# LONGAN_CORE.net
KiCad netlist of a schematic drawn in EAGLE
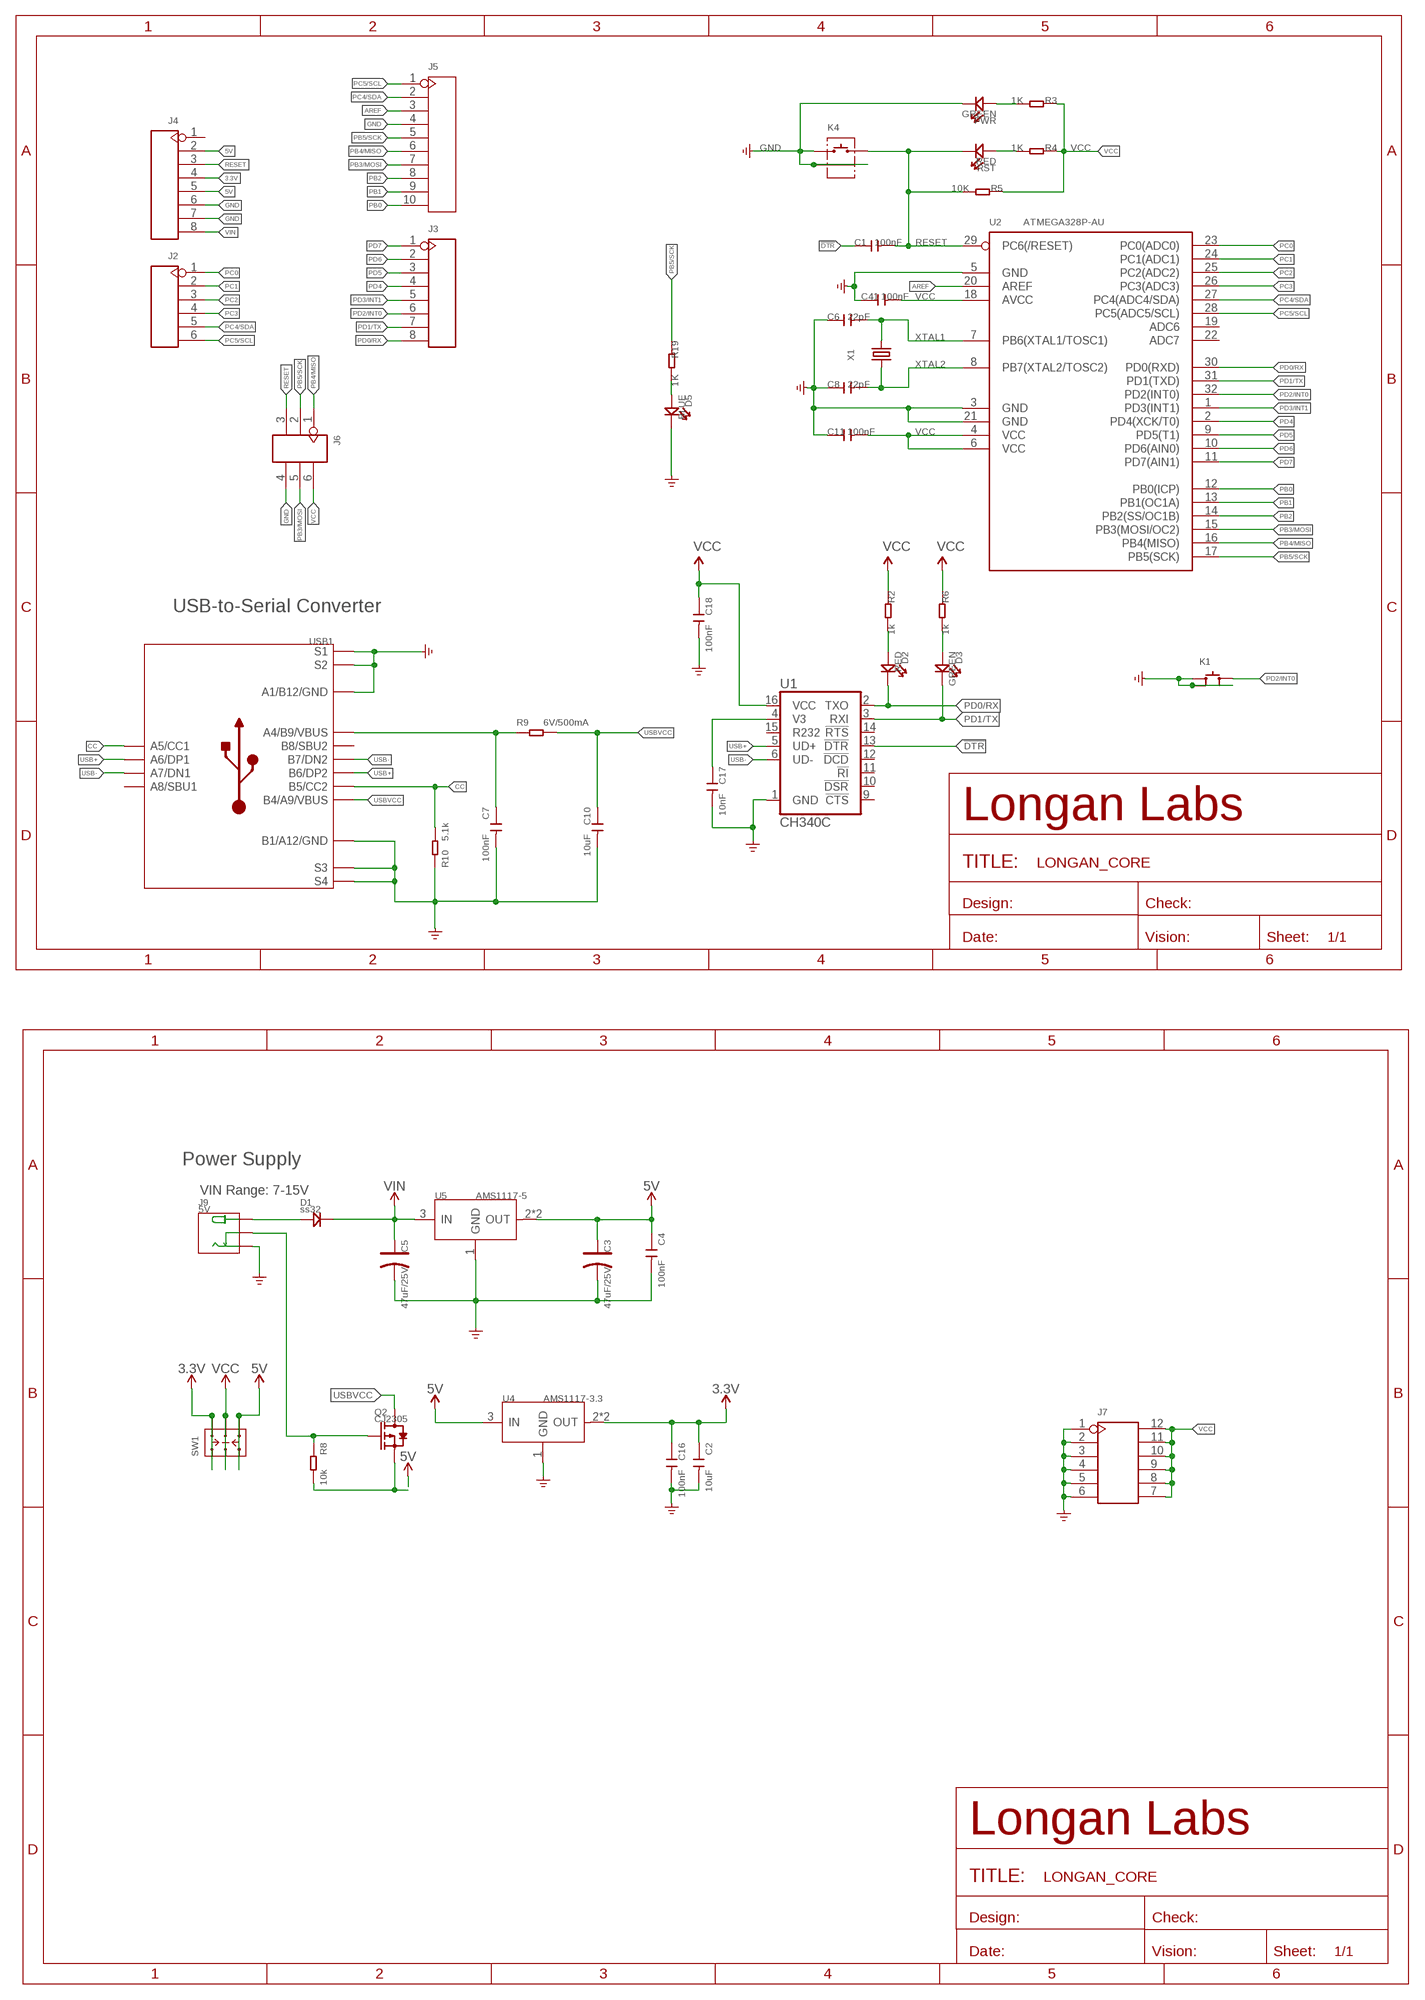
[diagram p0: schematic, sheet 1]

(export (version "E")
  (design (tool "Eeschema 10.0.6"))
  (components
    (comp (ref "C1")
      (value "100nF")
      (footprint "eagle-import:C0603")
      (libsource (lib "eagle-import") (part "C-0603"))
    )
    (comp (ref "C2")
      (value "10uF")
      (footprint "eagle-import:C0603")
      (libsource (lib "eagle-import") (part "CAP-0603"))
    )
    (comp (ref "C3")
      (value "47uF/25V")
      (footprint "eagle-import:ELECTRO-SMD-C-6MM")
      (libsource (lib "eagle-import") (part "CAP-POLAR-ELECTRO-C"))
    )
    (comp (ref "C4")
      (value "100nF")
      (footprint "eagle-import:C0603")
      (libsource (lib "eagle-import") (part "CAP-0603"))
    )
    (comp (ref "C5")
      (value "47uF/25V")
      (footprint "eagle-import:ELECTRO-SMD-C-6MM")
      (libsource (lib "eagle-import") (part "CAP-POLAR-ELECTRO-C"))
    )
    (comp (ref "C6")
      (value "22pF")
      (footprint "eagle-import:C0603")
      (libsource (lib "eagle-import") (part "C-0603"))
    )
    (comp (ref "C7")
      (value "100nF")
      (footprint "eagle-import:C0603")
      (libsource (lib "eagle-import") (part "CAP-0603"))
    )
    (comp (ref "C8")
      (value "22pF")
      (footprint "eagle-import:C0603")
      (libsource (lib "eagle-import") (part "C-0603"))
    )
    (comp (ref "C10")
      (value "10uF")
      (footprint "eagle-import:C0603")
      (libsource (lib "eagle-import") (part "CAP-0603"))
    )
    (comp (ref "C11")
      (value "100nF")
      (footprint "eagle-import:C0603")
      (libsource (lib "eagle-import") (part "C-0603"))
    )
    (comp (ref "C16")
      (value "100nF")
      (footprint "eagle-import:C0603")
      (libsource (lib "eagle-import") (part "CAP-0603"))
    )
    (comp (ref "C17")
      (value "10nF")
      (footprint "eagle-import:C0603")
      (libsource (lib "eagle-import") (part "CAP-0603"))
    )
    (comp (ref "C18")
      (value "100nF")
      (footprint "eagle-import:C0603")
      (libsource (lib "eagle-import") (part "CAP-0603"))
    )
    (comp (ref "C41")
      (value "100nF")
      (footprint "eagle-import:C0603")
      (libsource (lib "eagle-import") (part "C-0603"))
    )
    (comp (ref "D1")
      (value "ss32")
      (footprint "eagle-import:DO-214AC")
      (libsource (lib "eagle-import") (part "DIODE'SMA'"))
    )
    (comp (ref "D2")
      (value "RED")
      (footprint "eagle-import:LED-0603")
      (libsource (lib "eagle-import") (part "LED'0603'"))
    )
    (comp (ref "D3")
      (value "GREEN")
      (footprint "eagle-import:LED-0603")
      (libsource (lib "eagle-import") (part "LED'0603'"))
    )
    (comp (ref "D5")
      (value "BLUE")
      (footprint "eagle-import:LED-0603")
      (libsource (lib "eagle-import") (part "LED'0603'"))
    )
    (comp (ref "J2")
      (value "HEADER-6P-55/35MIL")
      (footprint "eagle-import:H6-2.54")
      (libsource (lib "eagle-import") (part "HEADER-6P-55/35MIL"))
    )
    (comp (ref "J3")
      (value "HEADER-8P-65/35MIL")
      (footprint "eagle-import:H8-2.54-C65D35MIL")
      (libsource (lib "eagle-import") (part "HEADER-8P-65/35MIL"))
    )
    (comp (ref "J4")
      (value "HEADER-8P-65/35MIL")
      (footprint "eagle-import:H8-2.54-C65D35MIL")
      (libsource (lib "eagle-import") (part "HEADER-8P-65/35MIL"))
    )
    (comp (ref "J5")
      (value "HEADER-10P-2.54")
      (footprint "eagle-import:H10-2.54")
      (libsource (lib "eagle-import") (part "HEADER-10P-2.54"))
    )
    (comp (ref "J6")
      (value "HEADER-2X3P-2.54")
      (footprint "eagle-import:H2X3-2.54")
      (libsource (lib "eagle-import") (part "HEADER-2X3P-2.54"))
    )
    (comp (ref "J7")
      (value "HEADER-2X6P-2.54")
      (footprint "eagle-import:H2X6-2.54")
      (libsource (lib "eagle-import") (part "HEADER-2X6P-2.54"))
    )
    (comp (ref "J9")
      (value "5V")
      (footprint "eagle-import:DCJ3P-14.2X11.0X9.0MM")
      (libsource (lib "eagle-import") (part "POWER-JACK-DC-320120003"))
    )
    (comp (ref "K1")
      (value "BUTTON-4P-6.2X6.2")
      (footprint "eagle-import:SW4-SMD-6.2X6.2MM")
      (libsource (lib "eagle-import") (part "BUTTON-4P-6.2X6.2"))
    )
    (comp (ref "K4")
      (value "BUTTON-2+2P")
      (footprint "eagle-import:SW2+2P-7.7X2.75X3.95MM")
      (libsource (lib "eagle-import") (part "BUTTON-2+2P"))
    )
    (comp (ref "PWR")
      (value "GREEN")
      (footprint "eagle-import:LED-0603")
      (libsource (lib "eagle-import") (part "LED'0603'"))
    )
    (comp (ref "Q2")
      (value "CJ2305")
      (footprint "eagle-import:SOT-23")
      (libsource (lib "eagle-import") (part "MOSFET-P'SI2323CDS/SI2305DS{lt}BR{gt}'"))
    )
    (comp (ref "R2")
      (value "1k")
      (footprint "eagle-import:R0603")
      (libsource (lib "eagle-import") (part "R-0603"))
    )
    (comp (ref "R3")
      (value "1K")
      (footprint "eagle-import:R0603")
      (libsource (lib "eagle-import") (part "R-0603"))
    )
    (comp (ref "R4")
      (value "1K")
      (footprint "eagle-import:R0603")
      (libsource (lib "eagle-import") (part "R-0603"))
    )
    (comp (ref "R5")
      (value "10K")
      (footprint "eagle-import:R0603")
      (libsource (lib "eagle-import") (part "R-0603"))
    )
    (comp (ref "R6")
      (value "1k")
      (footprint "eagle-import:R0603")
      (libsource (lib "eagle-import") (part "R-0603"))
    )
    (comp (ref "R8")
      (value "10k")
      (footprint "eagle-import:R0603")
      (libsource (lib "eagle-import") (part "RES-0603"))
    )
    (comp (ref "R9")
      (value "6V/500mA")
      (footprint "eagle-import:R0805")
      (libsource (lib "eagle-import") (part "RES-0805"))
    )
    (comp (ref "R10")
      (value "5.1k")
      (footprint "eagle-import:R0603")
      (libsource (lib "eagle-import") (part "RES-0603"))
    )
    (comp (ref "R19")
      (value "1K")
      (footprint "eagle-import:R0603")
      (libsource (lib "eagle-import") (part "R-0603"))
    )
    (comp (ref "RST")
      (value "RED")
      (footprint "eagle-import:LED-0603")
      (libsource (lib "eagle-import") (part "LED'0603'"))
    )
    (comp (ref "SW1")
      (value "SWITCH-2CH-6P-311010004")
      (footprint "eagle-import:SW6-2.54-9.0X3.5X3.2+2.0MM")
      (libsource (lib "eagle-import") (part "SWITCH-2CH-6P-311010004"))
    )
    (comp (ref "U1")
      (value "CH340C")
      (footprint "eagle-import:SO016")
      (libsource (lib "eagle-import") (part "CH340C"))
    )
    (comp (ref "U2")
      (value "ATMEGA328P-AU")
      (footprint "eagle-import:TQFP32-0.8-7X7MM")
      (libsource (lib "eagle-import") (part "MCU-ATMEGA8/168/328'AU'"))
    )
    (comp (ref "U4")
      (value "AMS1117-3.3")
      (footprint "eagle-import:SOT-223")
      (libsource (lib "eagle-import") (part "PMIC-CJ1117S"))
    )
    (comp (ref "U5")
      (value "AMS1117-5")
      (footprint "eagle-import:SOT-223")
      (libsource (lib "eagle-import") (part "PMIC-CJ1117S"))
    )
    (comp (ref "USB1")
      (value "TYPE-C-31-M-12")
      (footprint "eagle-import:USB2.0-TYPE-C")
      (libsource (lib "eagle-import") (part "USB2.0-TYPE-C"))
    )
    (comp (ref "X1")
      (value "16MHz")
      (footprint "eagle-import:HC49US")
      (libsource (lib "eagle-import") (part "CRYSTAL-2P'HC49US'"))
    )
  )
  (nets
    (net (code "1") (name "/XTAL1") (class "Default")
      (node (ref "C6") (pin "2") (pinfunction "2_2") (pintype "passive"))
      (node (ref "U2") (pin "7") (pinfunction "PB6(XTAL1/TOSC1)_7") (pintype "bidirectional"))
      (node (ref "X1") (pin "2") (pinfunction "2_2") (pintype "passive"))
    )
    (net (code "2") (name "/XTAL2") (class "Default")
      (node (ref "C8") (pin "2") (pinfunction "2_2") (pintype "passive"))
      (node (ref "U2") (pin "8") (pinfunction "PB7(XTAL2/TOSC2)_8") (pintype "bidirectional"))
      (node (ref "X1") (pin "1") (pinfunction "1_1") (pintype "passive"))
    )
    (net (code "3") (name "/~{DTR}") (class "Default")
      (node (ref "C1") (pin "1") (pinfunction "1_1") (pintype "passive"))
      (node (ref "U1") (pin "13") (pinfunction "~{DTR}_13") (pintype "bidirectional"))
    )
    (net (code "4") (name "3.3V") (class "Default")
      (node (ref "C16") (pin "1") (pinfunction "1_1") (pintype "passive"))
      (node (ref "C2") (pin "1") (pinfunction "1_1") (pintype "passive"))
      (node (ref "J4") (pin "4") (pinfunction "4_4") (pintype "bidirectional"))
      (node (ref "SW1") (pin "CH1A") (pinfunction "CH1A_CH1A") (pintype "bidirectional"))
      (node (ref "SW1") (pin "CH2A") (pinfunction "CH2A_CH2A") (pintype "bidirectional"))
      (node (ref "U4") (pin "2") (pinfunction "OUT_2") (pintype "bidirectional"))
      (node (ref "U4") (pin "TER") (pinfunction "OUT_TER") (pintype "bidirectional"))
    )
    (net (code "5") (name "5V") (class "Default")
      (node (ref "C3") (pin "+") (pinfunction "+_+") (pintype "passive"))
      (node (ref "C4") (pin "1") (pinfunction "1_1") (pintype "passive"))
      (node (ref "J4") (pin "2") (pinfunction "2_2") (pintype "bidirectional"))
      (node (ref "J4") (pin "5") (pinfunction "5_5") (pintype "bidirectional"))
      (node (ref "Q2") (pin "2") (pinfunction "S_2") (pintype "passive"))
      (node (ref "R8") (pin "2") (pinfunction "2_2") (pintype "passive"))
      (node (ref "SW1") (pin "CH1B") (pinfunction "CH1B_CH1B") (pintype "bidirectional"))
      (node (ref "SW1") (pin "CH2B") (pinfunction "CH2B_CH2B") (pintype "bidirectional"))
      (node (ref "U4") (pin "3") (pinfunction "IN_3") (pintype "bidirectional"))
      (node (ref "U5") (pin "2") (pinfunction "OUT_2") (pintype "bidirectional"))
      (node (ref "U5") (pin "TER") (pinfunction "OUT_TER") (pintype "bidirectional"))
    )
    (net (code "6") (name "AREF") (class "Default")
      (node (ref "J5") (pin "3") (pinfunction "3_3") (pintype "bidirectional"))
      (node (ref "U2") (pin "20") (pinfunction "AREF_20") (pintype "bidirectional"))
    )
    (net (code "7") (name "CC") (class "Default")
      (node (ref "R10") (pin "2") (pinfunction "2_2") (pintype "passive"))
      (node (ref "USB1") (pin "A5") (pinfunction "A5/CC1_A5") (pintype "bidirectional"))
      (node (ref "USB1") (pin "B5") (pinfunction "B5/CC2_B5") (pintype "bidirectional"))
    )
    (net (code "8") (name "GND") (class "Default")
      (node (ref "C10") (pin "2") (pinfunction "2_2") (pintype "passive"))
      (node (ref "C11") (pin "1") (pinfunction "1_1") (pintype "passive"))
      (node (ref "C16") (pin "2") (pinfunction "2_2") (pintype "passive"))
      (node (ref "C17") (pin "2") (pinfunction "2_2") (pintype "passive"))
      (node (ref "C18") (pin "2") (pinfunction "2_2") (pintype "passive"))
      (node (ref "C2") (pin "2") (pinfunction "2_2") (pintype "passive"))
      (node (ref "C3") (pin "-") (pinfunction "-_-") (pintype "passive"))
      (node (ref "C4") (pin "2") (pinfunction "2_2") (pintype "passive"))
      (node (ref "C41") (pin "1") (pinfunction "1_1") (pintype "passive"))
      (node (ref "C5") (pin "-") (pinfunction "-_-") (pintype "passive"))
      (node (ref "C6") (pin "1") (pinfunction "1_1") (pintype "passive"))
      (node (ref "C7") (pin "2") (pinfunction "2_2") (pintype "passive"))
      (node (ref "C8") (pin "1") (pinfunction "1_1") (pintype "passive"))
      (node (ref "D5") (pin "-") (pinfunction "-_-") (pintype "passive"))
      (node (ref "J4") (pin "6") (pinfunction "6_6") (pintype "bidirectional"))
      (node (ref "J4") (pin "7") (pinfunction "7_7") (pintype "bidirectional"))
      (node (ref "J5") (pin "4") (pinfunction "4_4") (pintype "bidirectional"))
      (node (ref "J6") (pin "4") (pinfunction "4_4") (pintype "bidirectional"))
      (node (ref "J7") (pin "1") (pinfunction "1_1") (pintype "bidirectional"))
      (node (ref "J7") (pin "2") (pinfunction "2_2") (pintype "bidirectional"))
      (node (ref "J7") (pin "3") (pinfunction "3_3") (pintype "bidirectional"))
      (node (ref "J7") (pin "4") (pinfunction "4_4") (pintype "bidirectional"))
      (node (ref "J7") (pin "5") (pinfunction "5_5") (pintype "bidirectional"))
      (node (ref "J7") (pin "6") (pinfunction "6_6") (pintype "bidirectional"))
      (node (ref "J9") (pin "-1") (pinfunction "-_-1") (pintype "bidirectional"))
      (node (ref "K1") (pin "1") (pinfunction "A0_1") (pintype "bidirectional"))
      (node (ref "K1") (pin "3") (pinfunction "B1_3") (pintype "bidirectional"))
      (node (ref "K1") (pin "4") (pinfunction "A1_4") (pintype "bidirectional"))
      (node (ref "K4") (pin "1") (pinfunction "1_1") (pintype "bidirectional"))
      (node (ref "K4") (pin "S1") (pinfunction "S1_S1") (pintype "bidirectional"))
      (node (ref "K4") (pin "S2") (pinfunction "S2_S2") (pintype "bidirectional"))
      (node (ref "PWR") (pin "-") (pinfunction "-_-") (pintype "passive"))
      (node (ref "R10") (pin "1") (pinfunction "1_1") (pintype "passive"))
      (node (ref "U1") (pin "1") (pinfunction "GND_1") (pintype "bidirectional"))
      (node (ref "U2") (pin "21") (pinfunction "GND_21") (pintype "bidirectional"))
      (node (ref "U2") (pin "3") (pinfunction "GND_3") (pintype "bidirectional"))
      (node (ref "U2") (pin "5") (pinfunction "GND_5") (pintype "bidirectional"))
      (node (ref "U4") (pin "1") (pinfunction "GND_1") (pintype "bidirectional"))
      (node (ref "U5") (pin "1") (pinfunction "GND_1") (pintype "bidirectional"))
      (node (ref "USB1") (pin "A1_B12") (pinfunction "A1/B12/GND_A1_B12") (pintype "bidirectional"))
      (node (ref "USB1") (pin "B1_A12") (pinfunction "B1/A12/GND_B1_A12") (pintype "bidirectional"))
      (node (ref "USB1") (pin "S1") (pinfunction "S1_S1") (pintype "bidirectional"))
      (node (ref "USB1") (pin "S2") (pinfunction "S2_S2") (pintype "bidirectional"))
      (node (ref "USB1") (pin "S3") (pinfunction "S3_S3") (pintype "bidirectional"))
      (node (ref "USB1") (pin "S4") (pinfunction "S4_S4") (pintype "bidirectional"))
      (node (ref "USB1") (pin "S5") (pinfunction "S1_S5") (pintype "bidirectional"))
      (node (ref "USB1") (pin "S6") (pinfunction "S2_S6") (pintype "bidirectional"))
    )
    (net (code "9") (name "Net-(D1-+)") (class "Default")
      (node (ref "D1") (pin "1") (pinfunction "+_1") (pintype "passive"))
      (node (ref "J9") (pin "+") (pinfunction "+_+") (pintype "bidirectional"))
    )
    (net (code "10") (name "Net-(D2-Pad+)") (class "Default")
      (node (ref "D2") (pin "+") (pinfunction "+_+") (pintype "passive"))
      (node (ref "R2") (pin "2") (pinfunction "2_2") (pintype "passive"))
    )
    (net (code "11") (name "Net-(D3-Pad+)") (class "Default")
      (node (ref "D3") (pin "+") (pinfunction "+_+") (pintype "passive"))
      (node (ref "R6") (pin "2") (pinfunction "2_2") (pintype "passive"))
    )
    (net (code "12") (name "Net-(D5-Pad+)") (class "Default")
      (node (ref "D5") (pin "+") (pinfunction "+_+") (pintype "passive"))
      (node (ref "R19") (pin "2") (pinfunction "2_2") (pintype "passive"))
    )
    (net (code "13") (name "Net-(J9-CDN)") (class "Default")
      (node (ref "J9") (pin "-2") (pinfunction "CDN_-2") (pintype "bidirectional"))
      (node (ref "Q2") (pin "1") (pinfunction "G_1") (pintype "passive"))
      (node (ref "R8") (pin "1") (pinfunction "1_1") (pintype "passive"))
    )
    (net (code "14") (name "Net-(PWR-Pad+)") (class "Default")
      (node (ref "PWR") (pin "+") (pinfunction "+_+") (pintype "passive"))
      (node (ref "R3") (pin "2") (pinfunction "2_2") (pintype "passive"))
    )
    (net (code "15") (name "Net-(R4-Pad2)") (class "Default")
      (node (ref "R4") (pin "2") (pinfunction "2_2") (pintype "passive"))
      (node (ref "RST") (pin "+") (pinfunction "+_+") (pintype "passive"))
    )
    (net (code "16") (name "Net-(U1-V3)") (class "Default")
      (node (ref "C17") (pin "1") (pinfunction "1_1") (pintype "passive"))
      (node (ref "U1") (pin "4") (pinfunction "V3_4") (pintype "bidirectional"))
    )
    (net (code "17") (name "Net-(USB1-A4{slash}B9{slash}VBUS)") (class "Default")
      (node (ref "C7") (pin "1") (pinfunction "1_1") (pintype "passive"))
      (node (ref "R9") (pin "1") (pinfunction "1_1") (pintype "passive"))
      (node (ref "USB1") (pin "A4_B9") (pinfunction "A4/B9/VBUS_A4_B9") (pintype "bidirectional"))
    )
    (net (code "18") (name "PB0") (class "Default")
      (node (ref "J5") (pin "10") (pinfunction "10_10") (pintype "bidirectional"))
      (node (ref "U2") (pin "12") (pinfunction "PB0(ICP)_12") (pintype "bidirectional"))
    )
    (net (code "19") (name "PB1") (class "Default")
      (node (ref "J5") (pin "9") (pinfunction "9_9") (pintype "bidirectional"))
      (node (ref "U2") (pin "13") (pinfunction "PB1(OC1A)_13") (pintype "bidirectional"))
    )
    (net (code "20") (name "PB2") (class "Default")
      (node (ref "J5") (pin "8") (pinfunction "8_8") (pintype "bidirectional"))
      (node (ref "U2") (pin "14") (pinfunction "PB2(SS/OC1B)_14") (pintype "bidirectional"))
    )
    (net (code "21") (name "PB3{slash}MOSI") (class "Default")
      (node (ref "J5") (pin "7") (pinfunction "7_7") (pintype "bidirectional"))
      (node (ref "J6") (pin "5") (pinfunction "5_5") (pintype "bidirectional"))
      (node (ref "U2") (pin "15") (pinfunction "PB3(MOSI/OC2)_15") (pintype "bidirectional"))
    )
    (net (code "22") (name "PB4{slash}MISO") (class "Default")
      (node (ref "J5") (pin "6") (pinfunction "6_6") (pintype "bidirectional"))
      (node (ref "J6") (pin "1") (pinfunction "1_1") (pintype "bidirectional"))
      (node (ref "U2") (pin "16") (pinfunction "PB4(MISO)_16") (pintype "bidirectional"))
    )
    (net (code "23") (name "PB5{slash}SCK") (class "Default")
      (node (ref "J5") (pin "5") (pinfunction "5_5") (pintype "bidirectional"))
      (node (ref "J6") (pin "2") (pinfunction "2_2") (pintype "bidirectional"))
      (node (ref "R19") (pin "1") (pinfunction "1_1") (pintype "passive"))
      (node (ref "U2") (pin "17") (pinfunction "PB5(SCK)_17") (pintype "bidirectional"))
    )
    (net (code "24") (name "PC0") (class "Default")
      (node (ref "J2") (pin "1") (pinfunction "1_1") (pintype "bidirectional"))
      (node (ref "U2") (pin "23") (pinfunction "PC0(ADC0)_23") (pintype "bidirectional"))
    )
    (net (code "25") (name "PC1") (class "Default")
      (node (ref "J2") (pin "2") (pinfunction "2_2") (pintype "bidirectional"))
      (node (ref "U2") (pin "24") (pinfunction "PC1(ADC1)_24") (pintype "bidirectional"))
    )
    (net (code "26") (name "PC2") (class "Default")
      (node (ref "J2") (pin "3") (pinfunction "3_3") (pintype "bidirectional"))
      (node (ref "U2") (pin "25") (pinfunction "PC2(ADC2)_25") (pintype "bidirectional"))
    )
    (net (code "27") (name "PC3") (class "Default")
      (node (ref "J2") (pin "4") (pinfunction "4_4") (pintype "bidirectional"))
      (node (ref "U2") (pin "26") (pinfunction "PC3(ADC3)_26") (pintype "bidirectional"))
    )
    (net (code "28") (name "PC4{slash}SDA") (class "Default")
      (node (ref "J2") (pin "5") (pinfunction "5_5") (pintype "bidirectional"))
      (node (ref "J5") (pin "2") (pinfunction "2_2") (pintype "bidirectional"))
      (node (ref "U2") (pin "27") (pinfunction "PC4(ADC4/SDA)_27") (pintype "bidirectional"))
    )
    (net (code "29") (name "PC5{slash}SCL") (class "Default")
      (node (ref "J2") (pin "6") (pinfunction "6_6") (pintype "bidirectional"))
      (node (ref "J5") (pin "1") (pinfunction "1_1") (pintype "bidirectional"))
      (node (ref "U2") (pin "28") (pinfunction "PC5(ADC5/SCL)_28") (pintype "bidirectional"))
    )
    (net (code "30") (name "PD0{slash}RX") (class "Default")
      (node (ref "D2") (pin "-") (pinfunction "-_-") (pintype "passive"))
      (node (ref "J3") (pin "8") (pinfunction "8_8") (pintype "bidirectional"))
      (node (ref "U1") (pin "2") (pinfunction "TXO_2") (pintype "bidirectional"))
      (node (ref "U2") (pin "30") (pinfunction "PD0(RXD)_30") (pintype "bidirectional"))
    )
    (net (code "31") (name "PD1{slash}TX") (class "Default")
      (node (ref "D3") (pin "-") (pinfunction "-_-") (pintype "passive"))
      (node (ref "J3") (pin "7") (pinfunction "7_7") (pintype "bidirectional"))
      (node (ref "U1") (pin "3") (pinfunction "RXI_3") (pintype "bidirectional"))
      (node (ref "U2") (pin "31") (pinfunction "PD1(TXD)_31") (pintype "bidirectional"))
    )
    (net (code "32") (name "PD2{slash}INT0") (class "Default")
      (node (ref "J3") (pin "6") (pinfunction "6_6") (pintype "bidirectional"))
      (node (ref "K1") (pin "2") (pinfunction "B0_2") (pintype "bidirectional"))
      (node (ref "U2") (pin "32") (pinfunction "PD2(INT0)_32") (pintype "bidirectional"))
    )
    (net (code "33") (name "PD3{slash}INT1") (class "Default")
      (node (ref "J3") (pin "5") (pinfunction "5_5") (pintype "bidirectional"))
      (node (ref "U2") (pin "1") (pinfunction "PD3(INT1)_1") (pintype "bidirectional"))
    )
    (net (code "34") (name "PD4") (class "Default")
      (node (ref "J3") (pin "4") (pinfunction "4_4") (pintype "bidirectional"))
      (node (ref "U2") (pin "2") (pinfunction "PD4(XCK/T0)_2") (pintype "bidirectional"))
    )
    (net (code "35") (name "PD5") (class "Default")
      (node (ref "J3") (pin "3") (pinfunction "3_3") (pintype "bidirectional"))
      (node (ref "U2") (pin "9") (pinfunction "PD5(T1)_9") (pintype "bidirectional"))
    )
    (net (code "36") (name "PD6") (class "Default")
      (node (ref "J3") (pin "2") (pinfunction "2_2") (pintype "bidirectional"))
      (node (ref "U2") (pin "10") (pinfunction "PD6(AIN0)_10") (pintype "bidirectional"))
    )
    (net (code "37") (name "PD7") (class "Default")
      (node (ref "J3") (pin "1") (pinfunction "1_1") (pintype "bidirectional"))
      (node (ref "U2") (pin "11") (pinfunction "PD7(AIN1)_11") (pintype "bidirectional"))
    )
    (net (code "38") (name "RESET") (class "Default")
      (node (ref "C1") (pin "2") (pinfunction "2_2") (pintype "passive"))
      (node (ref "J4") (pin "3") (pinfunction "3_3") (pintype "bidirectional"))
      (node (ref "J6") (pin "3") (pinfunction "3_3") (pintype "bidirectional"))
      (node (ref "K4") (pin "2") (pinfunction "2_2") (pintype "bidirectional"))
      (node (ref "R5") (pin "2") (pinfunction "2_2") (pintype "passive"))
      (node (ref "RST") (pin "-") (pinfunction "-_-") (pintype "passive"))
      (node (ref "U2") (pin "29") (pinfunction "PC6(/RESET)_29") (pintype "bidirectional"))
    )
    (net (code "39") (name "USB+") (class "Default")
      (node (ref "U1") (pin "5") (pinfunction "UD+_5") (pintype "bidirectional"))
      (node (ref "USB1") (pin "A6") (pinfunction "A6/DP1_A6") (pintype "bidirectional"))
      (node (ref "USB1") (pin "B6") (pinfunction "B6/DP2_B6") (pintype "bidirectional"))
    )
    (net (code "40") (name "USB-") (class "Default")
      (node (ref "U1") (pin "6") (pinfunction "UD-_6") (pintype "bidirectional"))
      (node (ref "USB1") (pin "A7") (pinfunction "A7/DN1_A7") (pintype "bidirectional"))
      (node (ref "USB1") (pin "B7") (pinfunction "B7/DN2_B7") (pintype "bidirectional"))
    )
    (net (code "41") (name "USBVCC") (class "Default")
      (node (ref "C10") (pin "1") (pinfunction "1_1") (pintype "passive"))
      (node (ref "Q2") (pin "3") (pinfunction "D_3") (pintype "passive"))
      (node (ref "R9") (pin "2") (pinfunction "2_2") (pintype "passive"))
      (node (ref "USB1") (pin "B4_A9") (pinfunction "B4/A9/VBUS_B4_A9") (pintype "bidirectional"))
    )
    (net (code "42") (name "VCC") (class "Default")
      (node (ref "C11") (pin "2") (pinfunction "2_2") (pintype "passive"))
      (node (ref "C18") (pin "1") (pinfunction "1_1") (pintype "passive"))
      (node (ref "C41") (pin "2") (pinfunction "2_2") (pintype "passive"))
      (node (ref "J6") (pin "6") (pinfunction "6_6") (pintype "bidirectional"))
      (node (ref "J7") (pin "10") (pinfunction "10_10") (pintype "bidirectional"))
      (node (ref "J7") (pin "11") (pinfunction "11_11") (pintype "bidirectional"))
      (node (ref "J7") (pin "12") (pinfunction "12_12") (pintype "bidirectional"))
      (node (ref "J7") (pin "7") (pinfunction "7_7") (pintype "bidirectional"))
      (node (ref "J7") (pin "8") (pinfunction "8_8") (pintype "bidirectional"))
      (node (ref "J7") (pin "9") (pinfunction "9_9") (pintype "bidirectional"))
      (node (ref "R2") (pin "1") (pinfunction "1_1") (pintype "passive"))
      (node (ref "R3") (pin "1") (pinfunction "1_1") (pintype "passive"))
      (node (ref "R4") (pin "1") (pinfunction "1_1") (pintype "passive"))
      (node (ref "R5") (pin "1") (pinfunction "1_1") (pintype "passive"))
      (node (ref "R6") (pin "1") (pinfunction "1_1") (pintype "passive"))
      (node (ref "SW1") (pin "COM1") (pinfunction "COM1_COM1") (pintype "bidirectional"))
      (node (ref "SW1") (pin "COM2") (pinfunction "COM2_COM2") (pintype "bidirectional"))
      (node (ref "U1") (pin "16") (pinfunction "VCC_16") (pintype "bidirectional"))
      (node (ref "U2") (pin "18") (pinfunction "AVCC_18") (pintype "bidirectional"))
      (node (ref "U2") (pin "4") (pinfunction "VCC_4") (pintype "bidirectional"))
      (node (ref "U2") (pin "6") (pinfunction "VCC_6") (pintype "bidirectional"))
    )
    (net (code "43") (name "VIN") (class "Default")
      (node (ref "C5") (pin "+") (pinfunction "+_+") (pintype "passive"))
      (node (ref "D1") (pin "2") (pinfunction "-_2") (pintype "passive"))
      (node (ref "J4") (pin "8") (pinfunction "8_8") (pintype "bidirectional"))
      (node (ref "U5") (pin "3") (pinfunction "IN_3") (pintype "bidirectional"))
    )
    (net (code "44") (name "unconnected-(J4-Pad1)") (class "Default")
      (node (ref "J4") (pin "1") (pinfunction "1_1") (pintype "bidirectional"))
    )
    (net (code "45") (name "unconnected-(U1-R232-Pad15)") (class "Default")
      (node (ref "U1") (pin "15") (pinfunction "R232_15") (pintype "bidirectional"))
    )
    (net (code "46") (name "unconnected-(U1-~{CTS}-Pad9)") (class "Default")
      (node (ref "U1") (pin "9") (pinfunction "~{CTS}_9") (pintype "bidirectional"))
    )
    (net (code "47") (name "unconnected-(U1-~{DCD}-Pad12)") (class "Default")
      (node (ref "U1") (pin "12") (pinfunction "~{DCD}_12") (pintype "bidirectional"))
    )
    (net (code "48") (name "unconnected-(U1-~{DSR}-Pad10)") (class "Default")
      (node (ref "U1") (pin "10") (pinfunction "~{DSR}_10") (pintype "bidirectional"))
    )
    (net (code "49") (name "unconnected-(U1-~{RI}-Pad11)") (class "Default")
      (node (ref "U1") (pin "11") (pinfunction "~{RI}_11") (pintype "bidirectional"))
    )
    (net (code "50") (name "unconnected-(U1-~{RTS}-Pad14)") (class "Default")
      (node (ref "U1") (pin "14") (pinfunction "~{RTS}_14") (pintype "bidirectional"))
    )
    (net (code "51") (name "unconnected-(U2-ADC6-Pad19)") (class "Default")
      (node (ref "U2") (pin "19") (pinfunction "ADC6_19") (pintype "bidirectional"))
    )
    (net (code "52") (name "unconnected-(U2-ADC7-Pad22)") (class "Default")
      (node (ref "U2") (pin "22") (pinfunction "ADC7_22") (pintype "bidirectional"))
    )
    (net (code "53") (name "unconnected-(USB1-A8{slash}SBU1-PadA8)") (class "Default")
      (node (ref "USB1") (pin "A8") (pinfunction "A8/SBU1_A8") (pintype "bidirectional"))
    )
    (net (code "54") (name "unconnected-(USB1-B8{slash}SBU2-PadB8)") (class "Default")
      (node (ref "USB1") (pin "B8") (pinfunction "B8/SBU2_B8") (pintype "bidirectional"))
    )
  )
)
